# APU.net
KiCad netlist of a schematic drawn in EAGLE
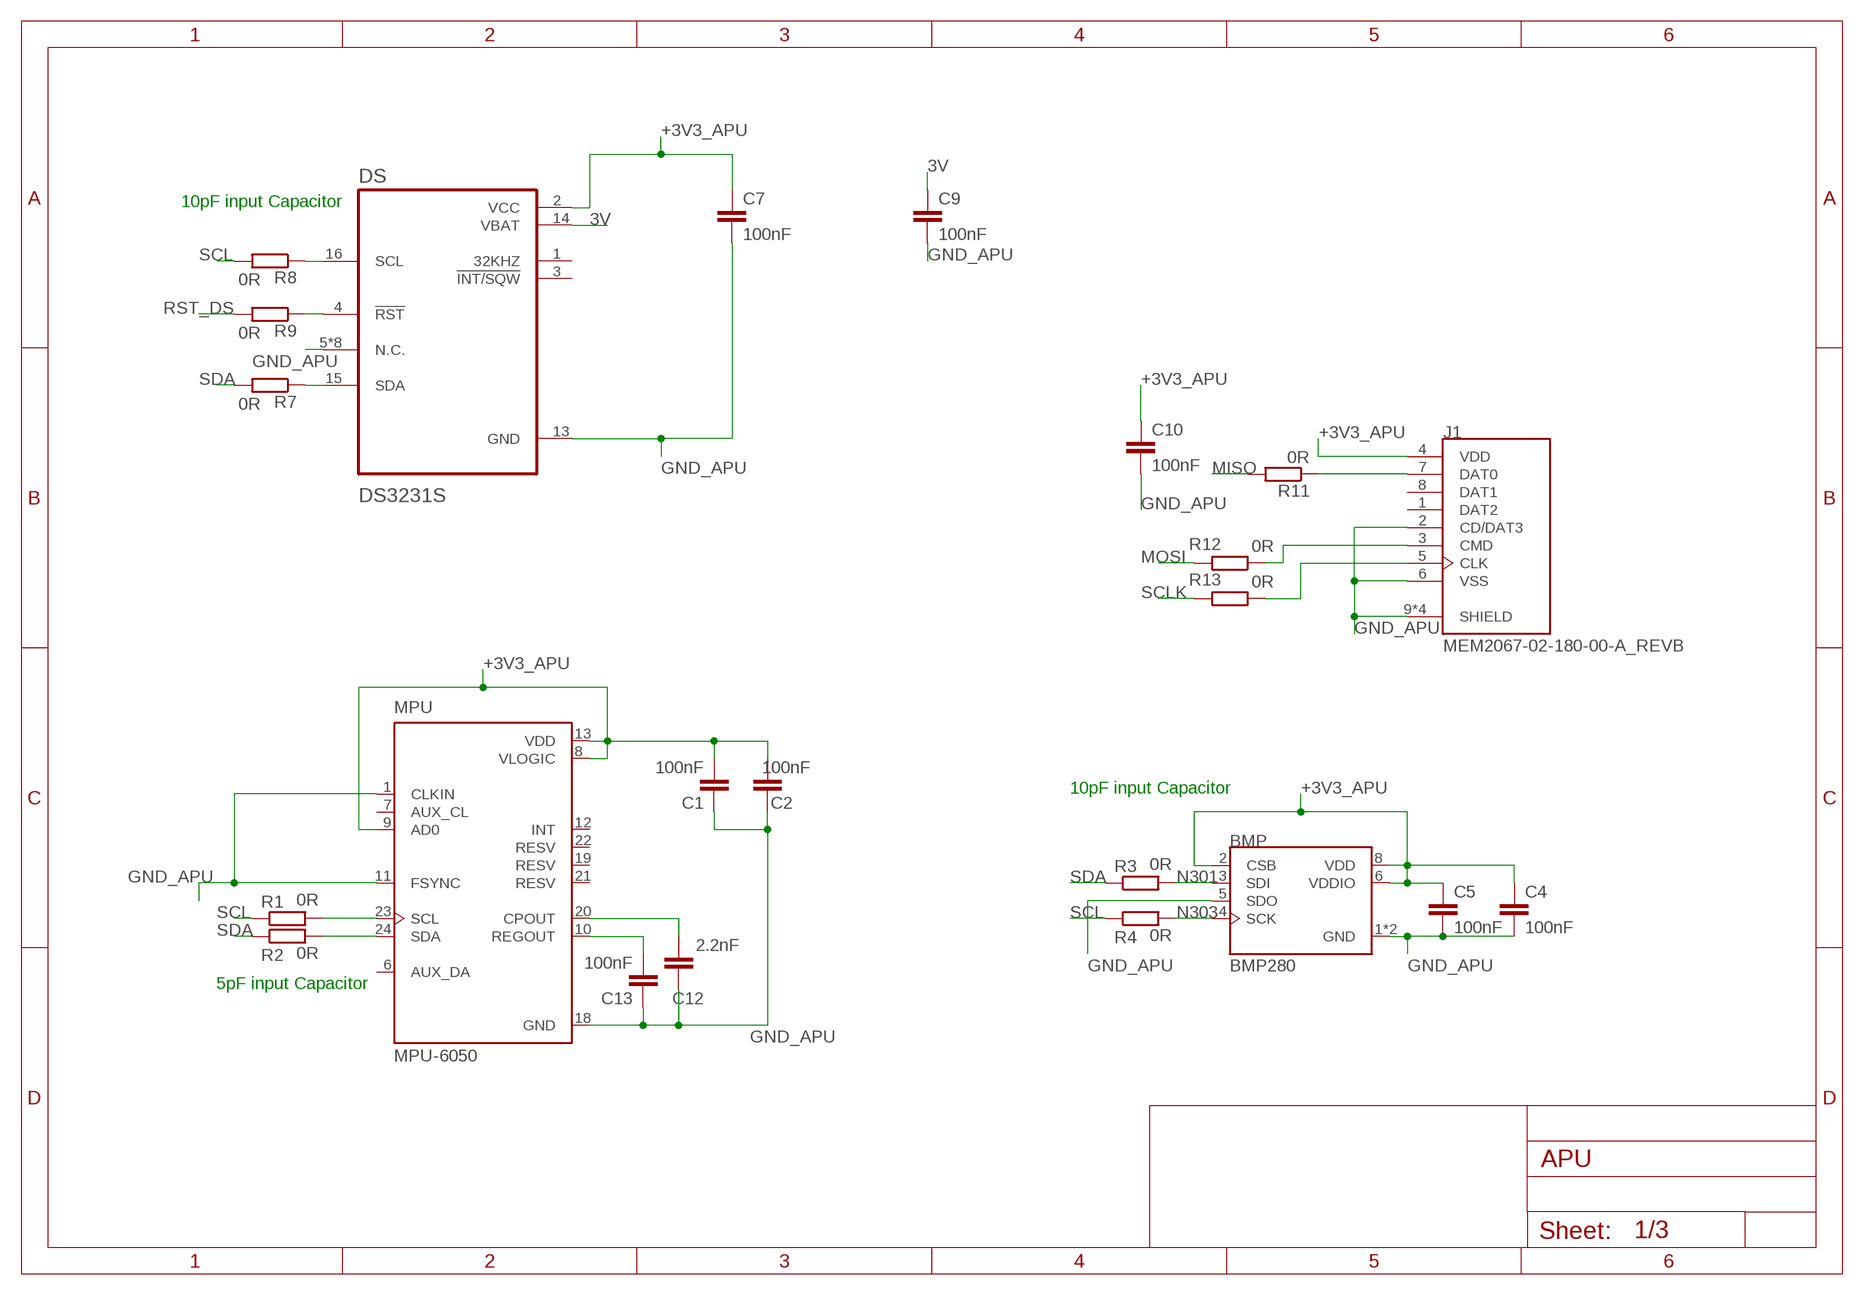
[diagram p0: schematic, sheet 1]
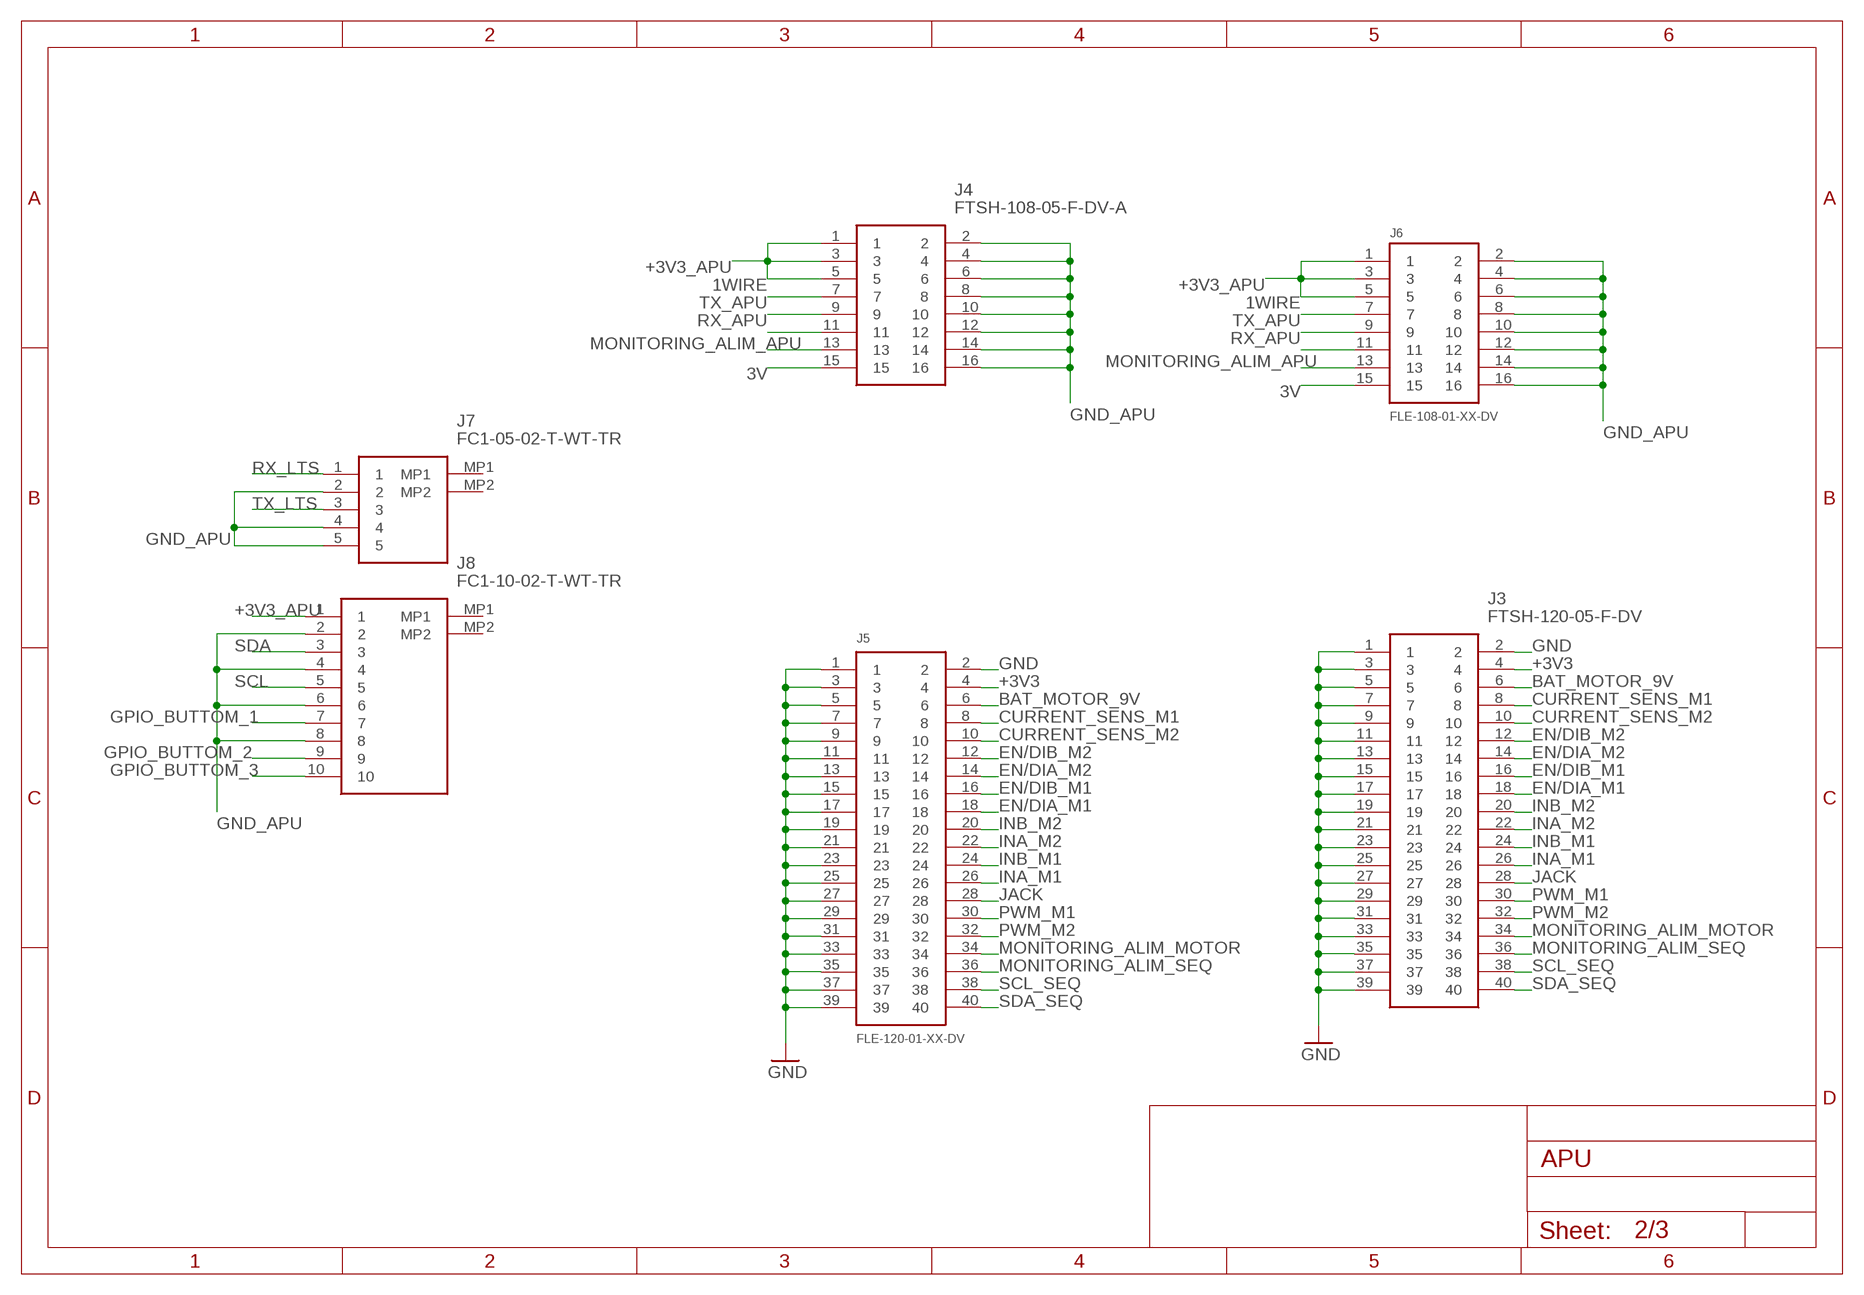
[diagram p1: schematic, sheet 2]
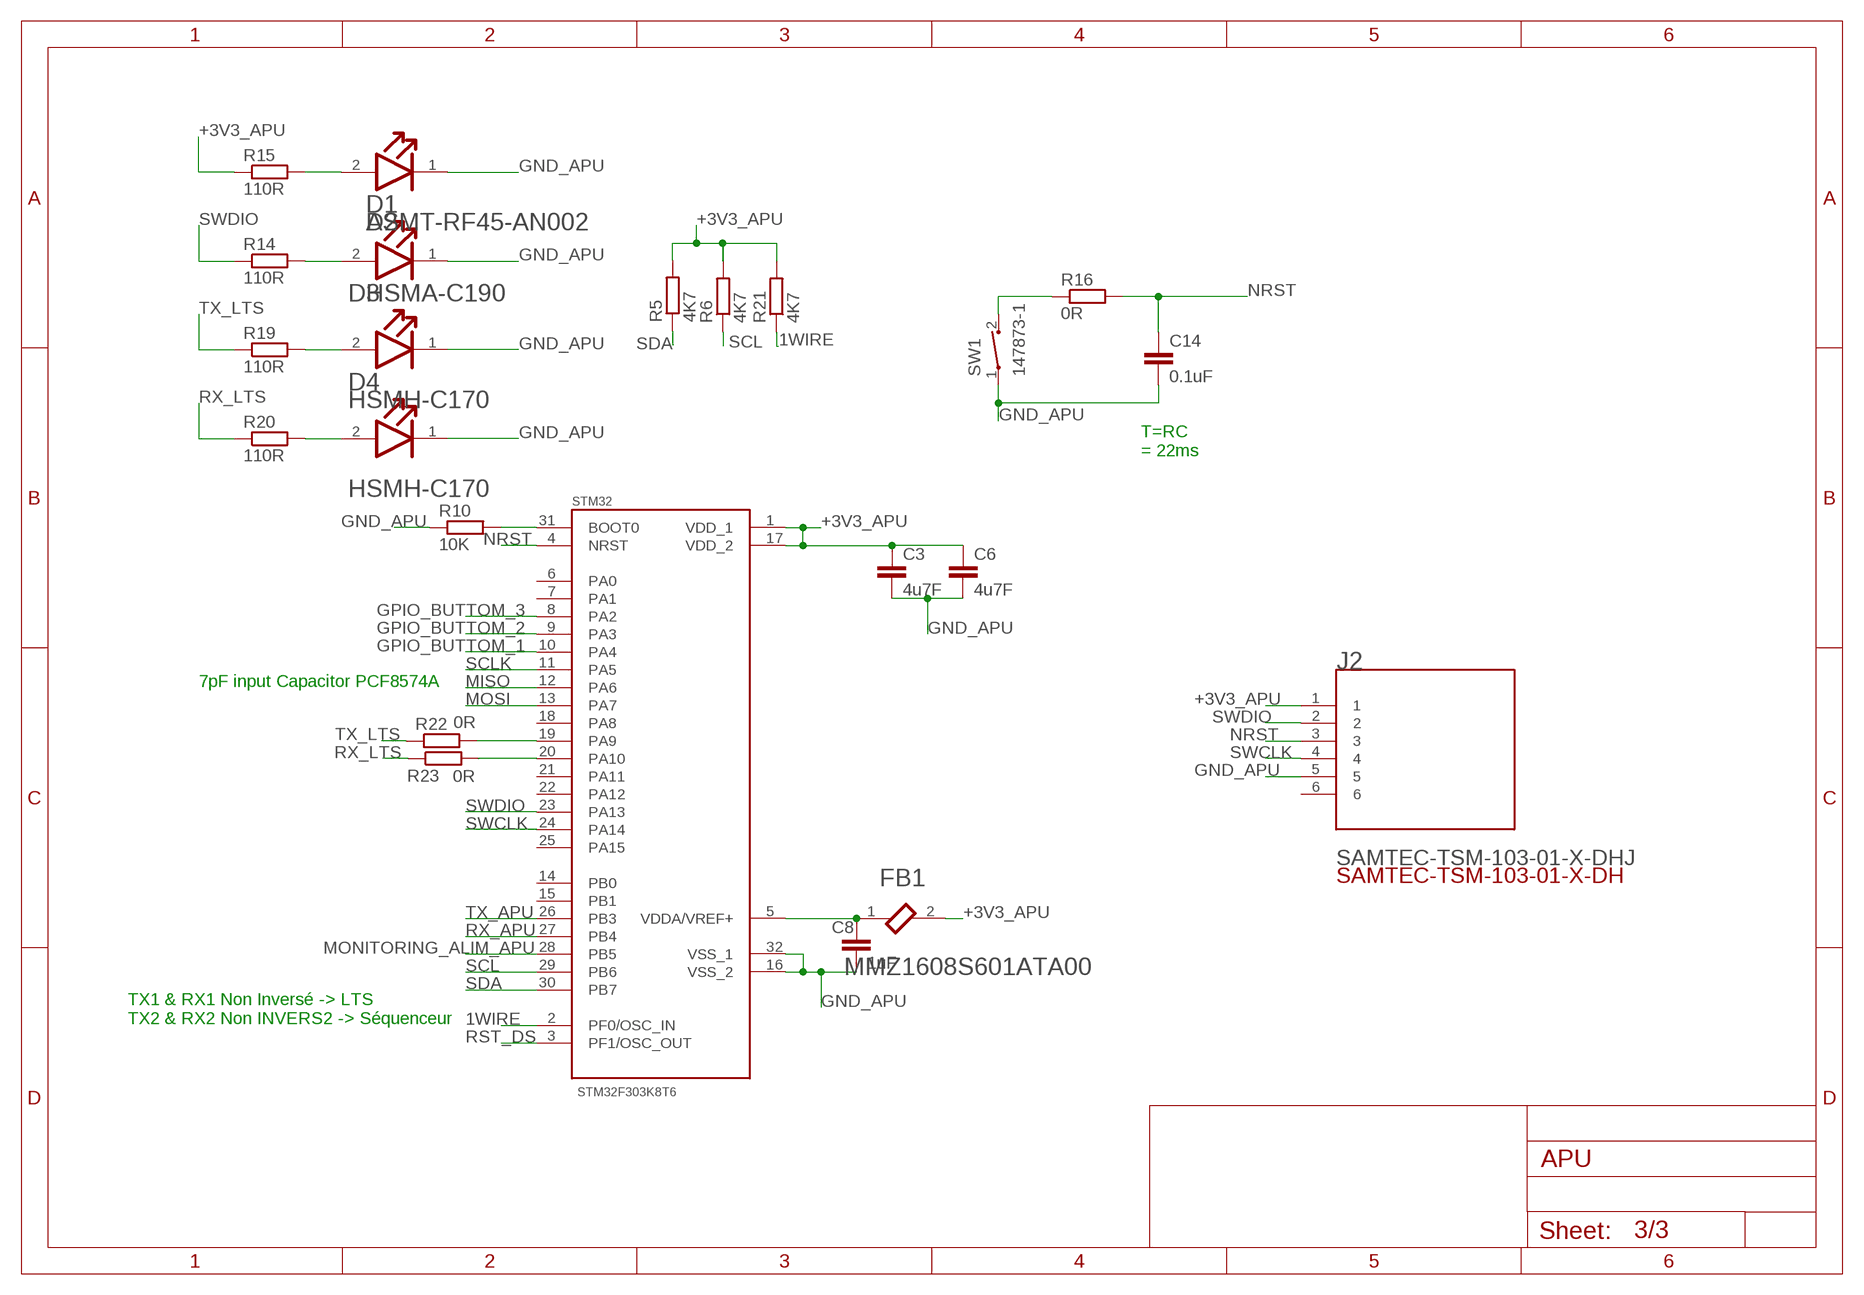
[diagram p2: schematic, sheet 3]

(export (version "E")
  (design (tool "Eeschema 10.0.6"))
  (components
    (comp (ref "BMP")
      (value "BMP280")
      (footprint "eagle-import:XDCR_BMP280")
      (fields (field (name "MF") "Bosch"))
      (libsource (lib "eagle-import") (part "BMP280"))
    )
    (comp (ref "C1")
      (value "100nF")
      (footprint "eagle-import:C0805")
      (libsource (lib "eagle-import") (part "C-EUC0805"))
    )
    (comp (ref "C2")
      (value "100nF")
      (footprint "eagle-import:C0805")
      (libsource (lib "eagle-import") (part "C-EUC0805"))
    )
    (comp (ref "C4")
      (value "100nF")
      (footprint "eagle-import:C0805")
      (libsource (lib "eagle-import") (part "C-EUC0805"))
    )
    (comp (ref "C5")
      (value "100nF")
      (footprint "eagle-import:C0805")
      (libsource (lib "eagle-import") (part "C-EUC0805"))
    )
    (comp (ref "C7")
      (value "100nF")
      (footprint "eagle-import:C0805")
      (libsource (lib "eagle-import") (part "C-EUC0805"))
    )
    (comp (ref "C9")
      (value "100nF")
      (footprint "eagle-import:C0805")
      (libsource (lib "eagle-import") (part "C-EUC0805"))
    )
    (comp (ref "C10")
      (value "100nF")
      (footprint "eagle-import:C0805")
      (libsource (lib "eagle-import") (part "C-EUC0805"))
    )
    (comp (ref "C12")
      (value "2.2nF")
      (footprint "eagle-import:C0805")
      (libsource (lib "eagle-import") (part "C-EUC0805"))
    )
    (comp (ref "C13")
      (value "100nF")
      (footprint "eagle-import:C0805")
      (libsource (lib "eagle-import") (part "C-EUC0805"))
    )
    (comp (ref "DS")
      (value "DS3231S")
      (footprint "eagle-import:SOIC127P1032X265-16N")
      (fields (field (name "MF") "Maxim Integrated"))
      (libsource (lib "eagle-import") (part "DS3231S"))
    )
    (comp (ref "J1")
      (value "MEM2067-02-180-00-A_REVB")
      (footprint "eagle-import:GCT_MEM2067-02-180-00-A_REVB")
      (fields (field (name "MF") "Global Connector Technology") (field (name "MP") "MEM2067-02-180-00-A"))
      (libsource (lib "eagle-import") (part "MEM2067-02-180-00-A_REVB"))
    )
    (comp (ref "MPU")
      (value "MPU-6050")
      (footprint "eagle-import:QFN50P400X400X95-24N")
      (fields (field (name "MF") "TDK InvenSense"))
      (libsource (lib "eagle-import") (part "MPU-6050"))
    )
    (comp (ref "R1")
      (value "0R")
      (footprint "eagle-import:R0603")
      (libsource (lib "eagle-import") (part "R-EU_R0603"))
    )
    (comp (ref "R2")
      (value "0R")
      (footprint "eagle-import:R0603")
      (libsource (lib "eagle-import") (part "R-EU_R0603"))
    )
    (comp (ref "R3")
      (value "0R")
      (footprint "eagle-import:R0603")
      (libsource (lib "eagle-import") (part "R-EU_R0603"))
    )
    (comp (ref "R4")
      (value "0R")
      (footprint "eagle-import:R0603")
      (libsource (lib "eagle-import") (part "R-EU_R0603"))
    )
    (comp (ref "R7")
      (value "0R")
      (footprint "eagle-import:R0603")
      (libsource (lib "eagle-import") (part "R-EU_R0603"))
    )
    (comp (ref "R8")
      (value "0R")
      (footprint "eagle-import:R0603")
      (libsource (lib "eagle-import") (part "R-EU_R0603"))
    )
    (comp (ref "R9")
      (value "0R")
      (footprint "eagle-import:R0603")
      (libsource (lib "eagle-import") (part "R-EU_R0603"))
    )
    (comp (ref "R11")
      (value "0R")
      (footprint "eagle-import:R0603")
      (libsource (lib "eagle-import") (part "R-EU_R0603"))
    )
    (comp (ref "R12")
      (value "0R")
      (footprint "eagle-import:R0603")
      (libsource (lib "eagle-import") (part "R-EU_R0603"))
    )
    (comp (ref "R13")
      (value "0R")
      (footprint "eagle-import:R0603")
      (libsource (lib "eagle-import") (part "R-EU_R0603"))
    )
    (comp (ref "C3")
      (value "4u7F")
      (footprint "eagle-import:C0805K")
      (libsource (lib "eagle-import") (part "C-EUC0805K"))
    )
    (comp (ref "C6")
      (value "4u7F")
      (footprint "eagle-import:C0805K")
      (libsource (lib "eagle-import") (part "C-EUC0805K"))
    )
    (comp (ref "C8")
      (value "1uF")
      (footprint "eagle-import:C0805K")
      (libsource (lib "eagle-import") (part "C-EUC0805K"))
    )
    (comp (ref "C14")
      (value "0.1uF")
      (footprint "eagle-import:C0805K")
      (libsource (lib "eagle-import") (part "C-EUC0805K"))
    )
    (comp (ref "D1")
      (value "BROADCOM_ASMT-RF45-AN002BROADCOM_ASMT-RF45-AN002_0_0")
      (footprint "eagle-import:BROADCOM_ASMT-RF45-AN002_0")
      (fields
        (field (name "DIGIKEY_PART_NUMBER") "516-2522-1-ND")
        (field (name "MF") "Broadcom")
        (field (name "MOUSER_PART_NUMBER") "630-ASMT-RF45-AN002")
      )
      (libsource (lib "eagle-import") (part "BROADCOM_ASMT-RF45-AN002BROADCOM_ASMT-RF45-AN002_0_0"))
    )
    (comp (ref "D2")
      (value "BROADCOM_HSMA-C190BROADCOM_HSMA-C190_0_0")
      (footprint "eagle-import:BROADCOM_HSMA-C190_0")
      (fields
        (field (name "DIGIKEY_PART_NUMBER") "516-1423-1-ND")
        (field (name "MF") "Broadcom")
        (field (name "MOUSER_PART_NUMBER") "630-HSMA-C190")
      )
      (libsource (lib "eagle-import") (part "BROADCOM_HSMA-C190BROADCOM_HSMA-C190_0_0"))
    )
    (comp (ref "D3")
      (value "BROADCOM_HSMH-C170BROADCOM_HSMH-C170_0_0")
      (footprint "eagle-import:BROADCOM_HSMH-C170_0")
      (fields
        (field (name "DIGIKEY_PART_NUMBER") "516-1427-1-ND")
        (field (name "MF") "Broadcom")
        (field (name "MOUSER_PART_NUMBER") "630-HSMH-C170")
      )
      (libsource (lib "eagle-import") (part "BROADCOM_HSMH-C170BROADCOM_HSMH-C170_0_0"))
    )
    (comp (ref "D4")
      (value "BROADCOM_HSMH-C170BROADCOM_HSMH-C170_0_0")
      (footprint "eagle-import:BROADCOM_HSMH-C170_0")
      (fields
        (field (name "DIGIKEY_PART_NUMBER") "516-1427-1-ND")
        (field (name "MF") "Broadcom")
        (field (name "MOUSER_PART_NUMBER") "630-HSMH-C170")
      )
      (libsource (lib "eagle-import") (part "BROADCOM_HSMH-C170BROADCOM_HSMH-C170_0_0"))
    )
    (comp (ref "FB1")
      (value "TDK_MMZ1608S601ATA00TDK_MMZ1608S601ATA00_0_0")
      (footprint "eagle-import:TDK_MMZ1608S601ATA00_0")
      (fields
        (field (name "MF") "TDK")
        (field (name "MPN") "MMZ1608S601ATA00")
        (field (name "TOLERANCE") "25%")
      )
      (libsource (lib "eagle-import") (part "TDK_MMZ1608S601ATA00TDK_MMZ1608S601ATA00_0_0"))
    )
    (comp (ref "J2")
      (value "SAMTEC-TSM-103-01-X-DHJ")
      (footprint "eagle-import:SAMTEC-TSM-103-01-X-DH")
      (fields (field (name "MF") "Samtec Inc.") (field (name "MP") "TSM-103-01-F-DH"))
      (libsource (lib "eagle-import") (part "SAMTEC-TSM-103-01-X-DHJ"))
    )
    (comp (ref "R5")
      (value "4K7")
      (footprint "eagle-import:R0603")
      (libsource (lib "eagle-import") (part "R-EU_R0603"))
    )
    (comp (ref "R6")
      (value "4K7")
      (footprint "eagle-import:R0603")
      (libsource (lib "eagle-import") (part "R-EU_R0603"))
    )
    (comp (ref "R10")
      (value "10K")
      (footprint "eagle-import:R0603")
      (libsource (lib "eagle-import") (part "R-EU_R0603"))
    )
    (comp (ref "R14")
      (value "110R")
      (footprint "eagle-import:R0603")
      (libsource (lib "eagle-import") (part "R-EU_R0603"))
    )
    (comp (ref "R15")
      (value "110R")
      (footprint "eagle-import:R0603")
      (libsource (lib "eagle-import") (part "R-EU_R0603"))
    )
    (comp (ref "R16")
      (value "0R")
      (footprint "eagle-import:R0603")
      (libsource (lib "eagle-import") (part "R-EU_R0603"))
    )
    (comp (ref "R19")
      (value "110R")
      (footprint "eagle-import:R0603")
      (libsource (lib "eagle-import") (part "R-EU_R0603"))
    )
    (comp (ref "R20")
      (value "110R")
      (footprint "eagle-import:R0603")
      (libsource (lib "eagle-import") (part "R-EU_R0603"))
    )
    (comp (ref "R21")
      (value "4K7")
      (footprint "eagle-import:R0603")
      (libsource (lib "eagle-import") (part "R-EU_R0603"))
    )
    (comp (ref "R22")
      (value "0R")
      (footprint "eagle-import:R0603")
      (libsource (lib "eagle-import") (part "R-EU_R0603"))
    )
    (comp (ref "R23")
      (value "0R")
      (footprint "eagle-import:R0603")
      (libsource (lib "eagle-import") (part "R-EU_R0603"))
    )
    (comp (ref "STM32")
      (value "STM32F303K8T6")
      (footprint "eagle-import:QFP80P900X900X160-32N")
      (fields (field (name "MANUFACTURER") "ST microelectronics"))
      (libsource (lib "eagle-import") (part "STM32F303K8T6"))
    )
    (comp (ref "SW1")
      (value "147873-1")
      (footprint "eagle-import:SW_147873-1")
      (fields (field (name "MF") "TE Connectivity"))
      (libsource (lib "eagle-import") (part "147873-1"))
    )
    (comp (ref "J3")
      (value "FTSH-120-05-F-DV")
      (footprint "eagle-import:FTSH-120-XX-YYY-DV")
      (libsource (lib "eagle-import") (part "FTSH-120-05-F-DV"))
    )
    (comp (ref "J4")
      (value "FTSH-108-05-F-DV-A")
      (footprint "eagle-import:FTSH-108-XX-YYY-DV-A")
      (fields (field (name "MOUSER_PART_NUMBER") "200-FTSH10805FDVA"))
      (libsource (lib "eagle-import") (part "FTSH-108-05-F-DV-A"))
    )
    (comp (ref "J5")
      (value "FLE-120-01-XX-DV")
      (footprint "eagle-import:FLE-120-01-XX-DV")
      (fields (field (name "MF") "Samtec") (field (name "MP") "FLE-120-01-G-DV"))
      (libsource (lib "eagle-import") (part "FLE-120-01-XX-DV"))
    )
    (comp (ref "J6")
      (value "FLE-108-01-XX-DV")
      (footprint "eagle-import:FLE-108-01-XX-DV")
      (fields (field (name "MF") "Samtec") (field (name "MP") "FLE-108-01-G-DV"))
      (libsource (lib "eagle-import") (part "FLE-108-01-XX-DV"))
    )
    (comp (ref "J7")
      (value "FC1-05-02-T-WT-TR")
      (footprint "eagle-import:FC10502TWTTR")
      (fields (field (name "MOUSER_PART_NUMBER") "200-FC10502TWTTR"))
      (libsource (lib "eagle-import") (part "FC1-05-02-T-WT-TR"))
    )
    (comp (ref "J8")
      (value "FC1-10-02-T-WT-TR")
      (footprint "eagle-import:FC11002TWTTR")
      (fields (field (name "MOUSER_PART_NUMBER") "200-FC11002TWTTR"))
      (libsource (lib "eagle-import") (part "FC1-10-02-T-WT-TR"))
    )
  )
  (nets
    (net (code "1") (name "+3V3") (class "Default")
      (node (ref "J3") (pin "4") (pinfunction "4_4") (pintype "bidirectional"))
      (node (ref "J5") (pin "4") (pinfunction "4_4") (pintype "bidirectional"))
    )
    (net (code "2") (name "+3V3_APU") (class "Default")
      (node (ref "BMP") (pin "2") (pinfunction "CSB_2") (pintype "input"))
      (node (ref "BMP") (pin "6") (pinfunction "VDDIO_6") (pintype "power_in"))
      (node (ref "BMP") (pin "8") (pinfunction "VDD_8") (pintype "power_in"))
      (node (ref "C1") (pin "2") (pinfunction "2_2") (pintype "passive"))
      (node (ref "C10") (pin "1") (pinfunction "1_1") (pintype "passive"))
      (node (ref "C2") (pin "2") (pinfunction "2_2") (pintype "passive"))
      (node (ref "C3") (pin "1") (pinfunction "1_1") (pintype "passive"))
      (node (ref "C4") (pin "1") (pinfunction "1_1") (pintype "passive"))
      (node (ref "C5") (pin "1") (pinfunction "1_1") (pintype "passive"))
      (node (ref "C6") (pin "1") (pinfunction "1_1") (pintype "passive"))
      (node (ref "C7") (pin "1") (pinfunction "1_1") (pintype "passive"))
      (node (ref "DS") (pin "2") (pinfunction "VCC_2") (pintype "power_in"))
      (node (ref "FB1") (pin "2") (pinfunction "2_2") (pintype "passive"))
      (node (ref "J1") (pin "4") (pinfunction "VDD_4") (pintype "power_in"))
      (node (ref "J2") (pin "1") (pinfunction "1_1") (pintype "bidirectional"))
      (node (ref "J4") (pin "1") (pinfunction "1_1") (pintype "bidirectional"))
      (node (ref "J4") (pin "3") (pinfunction "3_3") (pintype "bidirectional"))
      (node (ref "J4") (pin "5") (pinfunction "5_5") (pintype "bidirectional"))
      (node (ref "J6") (pin "1") (pinfunction "1_1") (pintype "bidirectional"))
      (node (ref "J6") (pin "3") (pinfunction "3_3") (pintype "bidirectional"))
      (node (ref "J6") (pin "5") (pinfunction "5_5") (pintype "bidirectional"))
      (node (ref "J8") (pin "1") (pinfunction "1_1") (pintype "bidirectional"))
      (node (ref "MPU") (pin "13") (pinfunction "VDD_13") (pintype "power_in"))
      (node (ref "MPU") (pin "8") (pinfunction "VLOGIC_8") (pintype "power_in"))
      (node (ref "MPU") (pin "9") (pinfunction "AD0_9") (pintype "input"))
      (node (ref "R15") (pin "1") (pinfunction "1_1") (pintype "passive"))
      (node (ref "R21") (pin "2") (pinfunction "2_2") (pintype "passive"))
      (node (ref "R5") (pin "2") (pinfunction "2_2") (pintype "passive"))
      (node (ref "R6") (pin "2") (pinfunction "2_2") (pintype "passive"))
      (node (ref "STM32") (pin "1") (pinfunction "VDD_1_1") (pintype "power_in"))
      (node (ref "STM32") (pin "17") (pinfunction "VDD_2_17") (pintype "power_in"))
    )
    (net (code "3") (name "1WIRE") (class "Default")
      (node (ref "J4") (pin "7") (pinfunction "7_7") (pintype "bidirectional"))
      (node (ref "J6") (pin "7") (pinfunction "7_7") (pintype "bidirectional"))
      (node (ref "R21") (pin "1") (pinfunction "1_1") (pintype "passive"))
      (node (ref "STM32") (pin "2") (pinfunction "PF0/OSC_IN_2") (pintype "bidirectional"))
    )
    (net (code "4") (name "3V") (class "Default")
      (node (ref "C9") (pin "1") (pinfunction "1_1") (pintype "passive"))
      (node (ref "DS") (pin "14") (pinfunction "VBAT_14") (pintype "power_in"))
      (node (ref "J4") (pin "15") (pinfunction "15_15") (pintype "bidirectional"))
      (node (ref "J6") (pin "15") (pinfunction "15_15") (pintype "bidirectional"))
    )
    (net (code "5") (name "BAT_MOTOR_9V") (class "Default")
      (node (ref "J3") (pin "6") (pinfunction "6_6") (pintype "bidirectional"))
      (node (ref "J5") (pin "6") (pinfunction "6_6") (pintype "bidirectional"))
    )
    (net (code "6") (name "CURRENT_SENS_M1") (class "Default")
      (node (ref "J3") (pin "8") (pinfunction "8_8") (pintype "bidirectional"))
      (node (ref "J5") (pin "8") (pinfunction "8_8") (pintype "bidirectional"))
    )
    (net (code "7") (name "CURRENT_SENS_M2") (class "Default")
      (node (ref "J3") (pin "10") (pinfunction "10_10") (pintype "bidirectional"))
      (node (ref "J5") (pin "10") (pinfunction "10_10") (pintype "bidirectional"))
    )
    (net (code "8") (name "EN{slash}DIA_M1") (class "Default")
      (node (ref "J3") (pin "18") (pinfunction "18_18") (pintype "bidirectional"))
      (node (ref "J5") (pin "18") (pinfunction "18_18") (pintype "bidirectional"))
    )
    (net (code "9") (name "EN{slash}DIA_M2") (class "Default")
      (node (ref "J3") (pin "14") (pinfunction "14_14") (pintype "bidirectional"))
      (node (ref "J5") (pin "14") (pinfunction "14_14") (pintype "bidirectional"))
    )
    (net (code "10") (name "EN{slash}DIB_M1") (class "Default")
      (node (ref "J3") (pin "16") (pinfunction "16_16") (pintype "bidirectional"))
      (node (ref "J5") (pin "16") (pinfunction "16_16") (pintype "bidirectional"))
    )
    (net (code "11") (name "EN{slash}DIB_M2") (class "Default")
      (node (ref "J3") (pin "12") (pinfunction "12_12") (pintype "bidirectional"))
      (node (ref "J5") (pin "12") (pinfunction "12_12") (pintype "bidirectional"))
    )
    (net (code "12") (name "GND") (class "Default")
      (node (ref "J3") (pin "1") (pinfunction "1_1") (pintype "bidirectional"))
      (node (ref "J3") (pin "11") (pinfunction "11_11") (pintype "bidirectional"))
      (node (ref "J3") (pin "13") (pinfunction "13_13") (pintype "bidirectional"))
      (node (ref "J3") (pin "15") (pinfunction "15_15") (pintype "bidirectional"))
      (node (ref "J3") (pin "17") (pinfunction "17_17") (pintype "bidirectional"))
      (node (ref "J3") (pin "19") (pinfunction "19_19") (pintype "bidirectional"))
      (node (ref "J3") (pin "2") (pinfunction "2_2") (pintype "bidirectional"))
      (node (ref "J3") (pin "21") (pinfunction "21_21") (pintype "bidirectional"))
      (node (ref "J3") (pin "23") (pinfunction "23_23") (pintype "bidirectional"))
      (node (ref "J3") (pin "25") (pinfunction "25_25") (pintype "bidirectional"))
      (node (ref "J3") (pin "27") (pinfunction "27_27") (pintype "bidirectional"))
      (node (ref "J3") (pin "29") (pinfunction "29_29") (pintype "bidirectional"))
      (node (ref "J3") (pin "3") (pinfunction "3_3") (pintype "bidirectional"))
      (node (ref "J3") (pin "31") (pinfunction "31_31") (pintype "bidirectional"))
      (node (ref "J3") (pin "33") (pinfunction "33_33") (pintype "bidirectional"))
      (node (ref "J3") (pin "35") (pinfunction "35_35") (pintype "bidirectional"))
      (node (ref "J3") (pin "37") (pinfunction "37_37") (pintype "bidirectional"))
      (node (ref "J3") (pin "39") (pinfunction "39_39") (pintype "bidirectional"))
      (node (ref "J3") (pin "5") (pinfunction "5_5") (pintype "bidirectional"))
      (node (ref "J3") (pin "7") (pinfunction "7_7") (pintype "bidirectional"))
      (node (ref "J3") (pin "9") (pinfunction "9_9") (pintype "bidirectional"))
      (node (ref "J5") (pin "1") (pinfunction "1_1") (pintype "bidirectional"))
      (node (ref "J5") (pin "11") (pinfunction "11_11") (pintype "bidirectional"))
      (node (ref "J5") (pin "13") (pinfunction "13_13") (pintype "bidirectional"))
      (node (ref "J5") (pin "15") (pinfunction "15_15") (pintype "bidirectional"))
      (node (ref "J5") (pin "17") (pinfunction "17_17") (pintype "bidirectional"))
      (node (ref "J5") (pin "19") (pinfunction "19_19") (pintype "bidirectional"))
      (node (ref "J5") (pin "2") (pinfunction "2_2") (pintype "bidirectional"))
      (node (ref "J5") (pin "21") (pinfunction "21_21") (pintype "bidirectional"))
      (node (ref "J5") (pin "23") (pinfunction "23_23") (pintype "bidirectional"))
      (node (ref "J5") (pin "25") (pinfunction "25_25") (pintype "bidirectional"))
      (node (ref "J5") (pin "27") (pinfunction "27_27") (pintype "bidirectional"))
      (node (ref "J5") (pin "29") (pinfunction "29_29") (pintype "bidirectional"))
      (node (ref "J5") (pin "3") (pinfunction "3_3") (pintype "bidirectional"))
      (node (ref "J5") (pin "31") (pinfunction "31_31") (pintype "bidirectional"))
      (node (ref "J5") (pin "33") (pinfunction "33_33") (pintype "bidirectional"))
      (node (ref "J5") (pin "35") (pinfunction "35_35") (pintype "bidirectional"))
      (node (ref "J5") (pin "37") (pinfunction "37_37") (pintype "bidirectional"))
      (node (ref "J5") (pin "39") (pinfunction "39_39") (pintype "bidirectional"))
      (node (ref "J5") (pin "5") (pinfunction "5_5") (pintype "bidirectional"))
      (node (ref "J5") (pin "7") (pinfunction "7_7") (pintype "bidirectional"))
      (node (ref "J5") (pin "9") (pinfunction "9_9") (pintype "bidirectional"))
    )
    (net (code "13") (name "GND_APU") (class "Default")
      (node (ref "BMP") (pin "1") (pinfunction "GND_1") (pintype "power_in"))
      (node (ref "BMP") (pin "5") (pinfunction "SDO_5") (pintype "bidirectional"))
      (node (ref "BMP") (pin "7") (pinfunction "GND_7") (pintype "power_in"))
      (node (ref "C1") (pin "1") (pinfunction "1_1") (pintype "passive"))
      (node (ref "C10") (pin "2") (pinfunction "2_2") (pintype "passive"))
      (node (ref "C12") (pin "1") (pinfunction "1_1") (pintype "passive"))
      (node (ref "C13") (pin "1") (pinfunction "1_1") (pintype "passive"))
      (node (ref "C14") (pin "2") (pinfunction "2_2") (pintype "passive"))
      (node (ref "C2") (pin "1") (pinfunction "1_1") (pintype "passive"))
      (node (ref "C3") (pin "2") (pinfunction "2_2") (pintype "passive"))
      (node (ref "C4") (pin "2") (pinfunction "2_2") (pintype "passive"))
      (node (ref "C5") (pin "2") (pinfunction "2_2") (pintype "passive"))
      (node (ref "C6") (pin "2") (pinfunction "2_2") (pintype "passive"))
      (node (ref "C7") (pin "2") (pinfunction "2_2") (pintype "passive"))
      (node (ref "C8") (pin "2") (pinfunction "2_2") (pintype "passive"))
      (node (ref "C9") (pin "2") (pinfunction "2_2") (pintype "passive"))
      (node (ref "D1") (pin "1") (pinfunction "CATHODE_1") (pintype "passive"))
      (node (ref "D2") (pin "1") (pinfunction "CATHODE_1") (pintype "passive"))
      (node (ref "D3") (pin "1") (pinfunction "CATHODE_1") (pintype "passive"))
      (node (ref "D4") (pin "1") (pinfunction "CATHODE_1") (pintype "passive"))
      (node (ref "DS") (pin "10") (pinfunction "N.C._10") (pintype "bidirectional"))
      (node (ref "DS") (pin "11") (pinfunction "N.C._11") (pintype "bidirectional"))
      (node (ref "DS") (pin "12") (pinfunction "N.C._12") (pintype "bidirectional"))
      (node (ref "DS") (pin "13") (pinfunction "GND_13") (pintype "power_in"))
      (node (ref "DS") (pin "5") (pinfunction "N.C._5") (pintype "bidirectional"))
      (node (ref "DS") (pin "6") (pinfunction "N.C._6") (pintype "bidirectional"))
      (node (ref "DS") (pin "7") (pinfunction "N.C._7") (pintype "bidirectional"))
      (node (ref "DS") (pin "8") (pinfunction "N.C._8") (pintype "bidirectional"))
      (node (ref "DS") (pin "9") (pinfunction "N.C._9") (pintype "bidirectional"))
      (node (ref "J1") (pin "10") (pinfunction "SHIELD_10") (pintype "passive"))
      (node (ref "J1") (pin "11") (pinfunction "SHIELD_11") (pintype "passive"))
      (node (ref "J1") (pin "12") (pinfunction "SHIELD_12") (pintype "passive"))
      (node (ref "J1") (pin "2") (pinfunction "CD/DAT3_2") (pintype "bidirectional"))
      (node (ref "J1") (pin "6") (pinfunction "VSS_6") (pintype "power_in"))
      (node (ref "J1") (pin "9") (pinfunction "SHIELD_9") (pintype "passive"))
      (node (ref "J2") (pin "5") (pinfunction "5_5") (pintype "bidirectional"))
      (node (ref "J4") (pin "10") (pinfunction "10_10") (pintype "bidirectional"))
      (node (ref "J4") (pin "12") (pinfunction "12_12") (pintype "bidirectional"))
      (node (ref "J4") (pin "14") (pinfunction "14_14") (pintype "bidirectional"))
      (node (ref "J4") (pin "16") (pinfunction "16_16") (pintype "bidirectional"))
      (node (ref "J4") (pin "2") (pinfunction "2_2") (pintype "bidirectional"))
      (node (ref "J4") (pin "4") (pinfunction "4_4") (pintype "bidirectional"))
      (node (ref "J4") (pin "6") (pinfunction "6_6") (pintype "bidirectional"))
      (node (ref "J4") (pin "8") (pinfunction "8_8") (pintype "bidirectional"))
      (node (ref "J6") (pin "10") (pinfunction "10_10") (pintype "bidirectional"))
      (node (ref "J6") (pin "12") (pinfunction "12_12") (pintype "bidirectional"))
      (node (ref "J6") (pin "14") (pinfunction "14_14") (pintype "bidirectional"))
      (node (ref "J6") (pin "16") (pinfunction "16_16") (pintype "bidirectional"))
      (node (ref "J6") (pin "2") (pinfunction "2_2") (pintype "bidirectional"))
      (node (ref "J6") (pin "4") (pinfunction "4_4") (pintype "bidirectional"))
      (node (ref "J6") (pin "6") (pinfunction "6_6") (pintype "bidirectional"))
      (node (ref "J6") (pin "8") (pinfunction "8_8") (pintype "bidirectional"))
      (node (ref "J7") (pin "2") (pinfunction "2_2") (pintype "bidirectional"))
      (node (ref "J7") (pin "4") (pinfunction "4_4") (pintype "bidirectional"))
      (node (ref "J7") (pin "5") (pinfunction "5_5") (pintype "bidirectional"))
      (node (ref "J8") (pin "2") (pinfunction "2_2") (pintype "bidirectional"))
      (node (ref "J8") (pin "4") (pinfunction "4_4") (pintype "bidirectional"))
      (node (ref "J8") (pin "6") (pinfunction "6_6") (pintype "bidirectional"))
      (node (ref "J8") (pin "8") (pinfunction "8_8") (pintype "bidirectional"))
      (node (ref "MPU") (pin "1") (pinfunction "CLKIN_1") (pintype "input"))
      (node (ref "MPU") (pin "11") (pinfunction "FSYNC_11") (pintype "input"))
      (node (ref "MPU") (pin "18") (pinfunction "GND_18") (pintype "power_in"))
      (node (ref "R10") (pin "1") (pinfunction "1_1") (pintype "passive"))
      (node (ref "STM32") (pin "16") (pinfunction "VSS_2_16") (pintype "power_in"))
      (node (ref "STM32") (pin "32") (pinfunction "VSS_1_32") (pintype "power_in"))
      (node (ref "SW1") (pin "1") (pinfunction "1_1") (pintype "passive"))
    )
    (net (code "14") (name "GPIO_BUTTOM_1") (class "Default")
      (node (ref "J8") (pin "7") (pinfunction "7_7") (pintype "bidirectional"))
      (node (ref "STM32") (pin "10") (pinfunction "PA4_10") (pintype "bidirectional"))
    )
    (net (code "15") (name "GPIO_BUTTOM_2") (class "Default")
      (node (ref "J8") (pin "9") (pinfunction "9_9") (pintype "bidirectional"))
      (node (ref "STM32") (pin "9") (pinfunction "PA3_9") (pintype "bidirectional"))
    )
    (net (code "16") (name "GPIO_BUTTOM_3") (class "Default")
      (node (ref "J8") (pin "10") (pinfunction "10_10") (pintype "bidirectional"))
      (node (ref "STM32") (pin "8") (pinfunction "PA2_8") (pintype "bidirectional"))
    )
    (net (code "17") (name "INA_M1") (class "Default")
      (node (ref "J3") (pin "26") (pinfunction "26_26") (pintype "bidirectional"))
      (node (ref "J5") (pin "26") (pinfunction "26_26") (pintype "bidirectional"))
    )
    (net (code "18") (name "INA_M2") (class "Default")
      (node (ref "J3") (pin "22") (pinfunction "22_22") (pintype "bidirectional"))
      (node (ref "J5") (pin "22") (pinfunction "22_22") (pintype "bidirectional"))
    )
    (net (code "19") (name "INB_M1") (class "Default")
      (node (ref "J3") (pin "24") (pinfunction "24_24") (pintype "bidirectional"))
      (node (ref "J5") (pin "24") (pinfunction "24_24") (pintype "bidirectional"))
    )
    (net (code "20") (name "INB_M2") (class "Default")
      (node (ref "J3") (pin "20") (pinfunction "20_20") (pintype "bidirectional"))
      (node (ref "J5") (pin "20") (pinfunction "20_20") (pintype "bidirectional"))
    )
    (net (code "21") (name "JACK") (class "Default")
      (node (ref "J3") (pin "28") (pinfunction "28_28") (pintype "bidirectional"))
      (node (ref "J5") (pin "28") (pinfunction "28_28") (pintype "bidirectional"))
    )
    (net (code "22") (name "MISO") (class "Default")
      (node (ref "R11") (pin "2") (pinfunction "2_2") (pintype "passive"))
      (node (ref "STM32") (pin "12") (pinfunction "PA6_12") (pintype "bidirectional"))
    )
    (net (code "23") (name "MONITORING_ALIM_APU") (class "Default")
      (node (ref "J4") (pin "13") (pinfunction "13_13") (pintype "bidirectional"))
      (node (ref "J6") (pin "13") (pinfunction "13_13") (pintype "bidirectional"))
      (node (ref "STM32") (pin "28") (pinfunction "PB5_28") (pintype "bidirectional"))
    )
    (net (code "24") (name "MONITORING_ALIM_MOTOR") (class "Default")
      (node (ref "J3") (pin "34") (pinfunction "34_34") (pintype "bidirectional"))
      (node (ref "J5") (pin "34") (pinfunction "34_34") (pintype "bidirectional"))
    )
    (net (code "25") (name "MONITORING_ALIM_SEQ") (class "Default")
      (node (ref "J3") (pin "36") (pinfunction "36_36") (pintype "bidirectional"))
      (node (ref "J5") (pin "36") (pinfunction "36_36") (pintype "bidirectional"))
    )
    (net (code "26") (name "MOSI") (class "Default")
      (node (ref "R12") (pin "2") (pinfunction "2_2") (pintype "passive"))
      (node (ref "STM32") (pin "13") (pinfunction "PA7_13") (pintype "bidirectional"))
    )
    (net (code "27") (name "N301") (class "Default")
      (node (ref "BMP") (pin "3") (pinfunction "SDI_3") (pintype "bidirectional"))
      (node (ref "R3") (pin "2") (pinfunction "2_2") (pintype "passive"))
    )
    (net (code "28") (name "N303") (class "Default")
      (node (ref "BMP") (pin "4") (pinfunction "SCK_4") (pintype "input"))
      (node (ref "R4") (pin "2") (pinfunction "2_2") (pintype "passive"))
    )
    (net (code "29") (name "NRST") (class "Default")
      (node (ref "C14") (pin "1") (pinfunction "1_1") (pintype "passive"))
      (node (ref "J2") (pin "3") (pinfunction "3_3") (pintype "bidirectional"))
      (node (ref "R16") (pin "2") (pinfunction "2_2") (pintype "passive"))
      (node (ref "STM32") (pin "4") (pinfunction "NRST_4") (pintype "bidirectional"))
    )
    (net (code "30") (name "Net-(D1-ANODE)") (class "Default")
      (node (ref "D1") (pin "2") (pinfunction "ANODE_2") (pintype "passive"))
      (node (ref "R15") (pin "2") (pinfunction "2_2") (pintype "passive"))
    )
    (net (code "31") (name "Net-(D2-ANODE)") (class "Default")
      (node (ref "D2") (pin "2") (pinfunction "ANODE_2") (pintype "passive"))
      (node (ref "R14") (pin "2") (pinfunction "2_2") (pintype "passive"))
    )
    (net (code "32") (name "Net-(D3-ANODE)") (class "Default")
      (node (ref "D3") (pin "2") (pinfunction "ANODE_2") (pintype "passive"))
      (node (ref "R19") (pin "2") (pinfunction "2_2") (pintype "passive"))
    )
    (net (code "33") (name "Net-(D4-ANODE)") (class "Default")
      (node (ref "D4") (pin "2") (pinfunction "ANODE_2") (pintype "passive"))
      (node (ref "R20") (pin "2") (pinfunction "2_2") (pintype "passive"))
    )
    (net (code "34") (name "Net-(DS-SCL)") (class "Default")
      (node (ref "DS") (pin "16") (pinfunction "SCL_16") (pintype "input"))
      (node (ref "R8") (pin "1") (pinfunction "1_1") (pintype "passive"))
    )
    (net (code "35") (name "Net-(DS-SDA)") (class "Default")
      (node (ref "DS") (pin "15") (pinfunction "SDA_15") (pintype "bidirectional"))
      (node (ref "R7") (pin "1") (pinfunction "1_1") (pintype "passive"))
    )
    (net (code "36") (name "Net-(DS-~{RST})") (class "Default")
      (node (ref "DS") (pin "4") (pinfunction "~{RST}_4") (pintype "bidirectional"))
      (node (ref "R9") (pin "1") (pinfunction "1_1") (pintype "passive"))
    )
    (net (code "37") (name "Net-(J1-CLK)") (class "Default")
      (node (ref "J1") (pin "5") (pinfunction "CLK_5") (pintype "bidirectional"))
      (node (ref "R13") (pin "1") (pinfunction "1_1") (pintype "passive"))
    )
    (net (code "38") (name "Net-(J1-CMD)") (class "Default")
      (node (ref "J1") (pin "3") (pinfunction "CMD_3") (pintype "bidirectional"))
      (node (ref "R12") (pin "1") (pinfunction "1_1") (pintype "passive"))
    )
    (net (code "39") (name "Net-(J1-DAT0)") (class "Default")
      (node (ref "J1") (pin "7") (pinfunction "DAT0_7") (pintype "bidirectional"))
      (node (ref "R11") (pin "1") (pinfunction "1_1") (pintype "passive"))
    )
    (net (code "40") (name "Net-(MPU-CPOUT)") (class "Default")
      (node (ref "C12") (pin "2") (pinfunction "2_2") (pintype "passive"))
      (node (ref "MPU") (pin "20") (pinfunction "CPOUT_20") (pintype "passive"))
    )
    (net (code "41") (name "Net-(MPU-REGOUT)") (class "Default")
      (node (ref "C13") (pin "2") (pinfunction "2_2") (pintype "passive"))
      (node (ref "MPU") (pin "10") (pinfunction "REGOUT_10") (pintype "passive"))
    )
    (net (code "42") (name "Net-(MPU-SCL)") (class "Default")
      (node (ref "MPU") (pin "23") (pinfunction "SCL_23") (pintype "input"))
      (node (ref "R1") (pin "2") (pinfunction "2_2") (pintype "passive"))
    )
    (net (code "43") (name "Net-(MPU-SDA)") (class "Default")
      (node (ref "MPU") (pin "24") (pinfunction "SDA_24") (pintype "bidirectional"))
      (node (ref "R2") (pin "2") (pinfunction "2_2") (pintype "passive"))
    )
    (net (code "44") (name "Net-(R16-Pad1)") (class "Default")
      (node (ref "R16") (pin "1") (pinfunction "1_1") (pintype "passive"))
      (node (ref "SW1") (pin "2") (pinfunction "2_2") (pintype "passive"))
    )
    (net (code "45") (name "Net-(STM32-BOOT0)") (class "Default")
      (node (ref "R10") (pin "2") (pinfunction "2_2") (pintype "passive"))
      (node (ref "STM32") (pin "31") (pinfunction "BOOT0_31") (pintype "input"))
    )
    (net (code "46") (name "Net-(STM32-PA9)") (class "Default")
      (node (ref "R22") (pin "2") (pinfunction "2_2") (pintype "passive"))
      (node (ref "STM32") (pin "19") (pinfunction "PA9_19") (pintype "bidirectional"))
    )
    (net (code "47") (name "Net-(STM32-PA10)") (class "Default")
      (node (ref "R23") (pin "2") (pinfunction "2_2") (pintype "passive"))
      (node (ref "STM32") (pin "20") (pinfunction "PA10_20") (pintype "bidirectional"))
    )
    (net (code "48") (name "Net-(STM32-VDDA{slash}VREF+)") (class "Default")
      (node (ref "C8") (pin "1") (pinfunction "1_1") (pintype "passive"))
      (node (ref "FB1") (pin "1") (pinfunction "1_1") (pintype "passive"))
      (node (ref "STM32") (pin "5") (pinfunction "VDDA/VREF+_5") (pintype "power_in"))
    )
    (net (code "49") (name "PWM_M1") (class "Default")
      (node (ref "J3") (pin "30") (pinfunction "30_30") (pintype "bidirectional"))
      (node (ref "J5") (pin "30") (pinfunction "30_30") (pintype "bidirectional"))
    )
    (net (code "50") (name "PWM_M2") (class "Default")
      (node (ref "J3") (pin "32") (pinfunction "32_32") (pintype "bidirectional"))
      (node (ref "J5") (pin "32") (pinfunction "32_32") (pintype "bidirectional"))
    )
    (net (code "51") (name "RST_DS") (class "Default")
      (node (ref "R9") (pin "2") (pinfunction "2_2") (pintype "passive"))
      (node (ref "STM32") (pin "3") (pinfunction "PF1/OSC_OUT_3") (pintype "bidirectional"))
    )
    (net (code "52") (name "RX_APU") (class "Default")
      (node (ref "J4") (pin "11") (pinfunction "11_11") (pintype "bidirectional"))
      (node (ref "J6") (pin "11") (pinfunction "11_11") (pintype "bidirectional"))
      (node (ref "STM32") (pin "27") (pinfunction "PB4_27") (pintype "bidirectional"))
    )
    (net (code "53") (name "RX_LTS") (class "Default")
      (node (ref "J7") (pin "1") (pinfunction "1_1") (pintype "bidirectional"))
      (node (ref "R20") (pin "1") (pinfunction "1_1") (pintype "passive"))
      (node (ref "R23") (pin "1") (pinfunction "1_1") (pintype "passive"))
    )
    (net (code "54") (name "SCL") (class "Default")
      (node (ref "J8") (pin "5") (pinfunction "5_5") (pintype "bidirectional"))
      (node (ref "R1") (pin "1") (pinfunction "1_1") (pintype "passive"))
      (node (ref "R4") (pin "1") (pinfunction "1_1") (pintype "passive"))
      (node (ref "R6") (pin "1") (pinfunction "1_1") (pintype "passive"))
      (node (ref "R8") (pin "2") (pinfunction "2_2") (pintype "passive"))
      (node (ref "STM32") (pin "29") (pinfunction "PB6_29") (pintype "bidirectional"))
    )
    (net (code "55") (name "SCLK") (class "Default")
      (node (ref "R13") (pin "2") (pinfunction "2_2") (pintype "passive"))
      (node (ref "STM32") (pin "11") (pinfunction "PA5_11") (pintype "bidirectional"))
    )
    (net (code "56") (name "SCL_SEQ") (class "Default")
      (node (ref "J3") (pin "38") (pinfunction "38_38") (pintype "bidirectional"))
      (node (ref "J5") (pin "38") (pinfunction "38_38") (pintype "bidirectional"))
    )
    (net (code "57") (name "SDA") (class "Default")
      (node (ref "J8") (pin "3") (pinfunction "3_3") (pintype "bidirectional"))
      (node (ref "R2") (pin "1") (pinfunction "1_1") (pintype "passive"))
      (node (ref "R3") (pin "1") (pinfunction "1_1") (pintype "passive"))
      (node (ref "R5") (pin "1") (pinfunction "1_1") (pintype "passive"))
      (node (ref "R7") (pin "2") (pinfunction "2_2") (pintype "passive"))
      (node (ref "STM32") (pin "30") (pinfunction "PB7_30") (pintype "bidirectional"))
    )
    (net (code "58") (name "SDA_SEQ") (class "Default")
      (node (ref "J3") (pin "40") (pinfunction "40_40") (pintype "bidirectional"))
      (node (ref "J5") (pin "40") (pinfunction "40_40") (pintype "bidirectional"))
    )
    (net (code "59") (name "SWCLK") (class "Default")
      (node (ref "J2") (pin "4") (pinfunction "4_4") (pintype "bidirectional"))
      (node (ref "STM32") (pin "24") (pinfunction "PA14_24") (pintype "bidirectional"))
    )
    (net (code "60") (name "SWDIO") (class "Default")
      (node (ref "J2") (pin "2") (pinfunction "2_2") (pintype "bidirectional"))
      (node (ref "R14") (pin "1") (pinfunction "1_1") (pintype "passive"))
      (node (ref "STM32") (pin "23") (pinfunction "PA13_23") (pintype "bidirectional"))
    )
    (net (code "61") (name "TX_APU") (class "Default")
      (node (ref "J4") (pin "9") (pinfunction "9_9") (pintype "bidirectional"))
      (node (ref "J6") (pin "9") (pinfunction "9_9") (pintype "bidirectional"))
      (node (ref "STM32") (pin "26") (pinfunction "PB3_26") (pintype "bidirectional"))
    )
    (net (code "62") (name "TX_LTS") (class "Default")
      (node (ref "J7") (pin "3") (pinfunction "3_3") (pintype "bidirectional"))
      (node (ref "R19") (pin "1") (pinfunction "1_1") (pintype "passive"))
      (node (ref "R22") (pin "1") (pinfunction "1_1") (pintype "passive"))
    )
    (net (code "63") (name "unconnected-(DS-32KHZ-Pad1)") (class "Default")
      (node (ref "DS") (pin "1") (pinfunction "32KHZ_1") (pintype "output"))
    )
    (net (code "64") (name "unconnected-(DS-~{INT{slash}SQW}-Pad3)") (class "Default")
      (node (ref "DS") (pin "3") (pinfunction "~{INT/SQW}_3") (pintype "output"))
    )
    (net (code "65") (name "unconnected-(J1-DAT1-Pad8)") (class "Default")
      (node (ref "J1") (pin "8") (pinfunction "DAT1_8") (pintype "bidirectional"))
    )
    (net (code "66") (name "unconnected-(J1-DAT2-Pad1)") (class "Default")
      (node (ref "J1") (pin "1") (pinfunction "DAT2_1") (pintype "bidirectional"))
    )
    (net (code "67") (name "unconnected-(J2-Pad6)") (class "Default")
      (node (ref "J2") (pin "6") (pinfunction "6_6") (pintype "bidirectional"))
    )
    (net (code "68") (name "unconnected-(J7-PadMP1)") (class "Default")
      (node (ref "J7") (pin "MP1") (pinfunction "MP1_MP1") (pintype "bidirectional"))
    )
    (net (code "69") (name "unconnected-(J7-PadMP2)") (class "Default")
      (node (ref "J7") (pin "MP2") (pinfunction "MP2_MP2") (pintype "bidirectional"))
    )
    (net (code "70") (name "unconnected-(J8-PadMP1)") (class "Default")
      (node (ref "J8") (pin "MP1") (pinfunction "MP1_MP1") (pintype "bidirectional"))
    )
    (net (code "71") (name "unconnected-(J8-PadMP2)") (class "Default")
      (node (ref "J8") (pin "MP2") (pinfunction "MP2_MP2") (pintype "bidirectional"))
    )
    (net (code "72") (name "unconnected-(MPU-AUX_CL-Pad7)") (class "Default")
      (node (ref "MPU") (pin "7") (pinfunction "AUX_CL_7") (pintype "input"))
    )
    (net (code "73") (name "unconnected-(MPU-AUX_DA-Pad6)") (class "Default")
      (node (ref "MPU") (pin "6") (pinfunction "AUX_DA_6") (pintype "bidirectional"))
    )
    (net (code "74") (name "unconnected-(MPU-INT-Pad12)") (class "Default")
      (node (ref "MPU") (pin "12") (pinfunction "INT_12") (pintype "output"))
    )
    (net (code "75") (name "unconnected-(MPU-RESV-Pad19)") (class "Default")
      (node (ref "MPU") (pin "19") (pinfunction "RESV_19") (pintype "passive"))
    )
    (net (code "76") (name "unconnected-(MPU-RESV-Pad21)") (class "Default")
      (node (ref "MPU") (pin "21") (pinfunction "RESV_21") (pintype "passive"))
    )
    (net (code "77") (name "unconnected-(MPU-RESV-Pad22)") (class "Default")
      (node (ref "MPU") (pin "22") (pinfunction "RESV_22") (pintype "passive"))
    )
    (net (code "78") (name "unconnected-(STM32-PA0-Pad6)") (class "Default")
      (node (ref "STM32") (pin "6") (pinfunction "PA0_6") (pintype "bidirectional"))
    )
    (net (code "79") (name "unconnected-(STM32-PA1-Pad7)") (class "Default")
      (node (ref "STM32") (pin "7") (pinfunction "PA1_7") (pintype "bidirectional"))
    )
    (net (code "80") (name "unconnected-(STM32-PA8-Pad18)") (class "Default")
      (node (ref "STM32") (pin "18") (pinfunction "PA8_18") (pintype "bidirectional"))
    )
    (net (code "81") (name "unconnected-(STM32-PA11-Pad21)") (class "Default")
      (node (ref "STM32") (pin "21") (pinfunction "PA11_21") (pintype "bidirectional"))
    )
    (net (code "82") (name "unconnected-(STM32-PA12-Pad22)") (class "Default")
      (node (ref "STM32") (pin "22") (pinfunction "PA12_22") (pintype "bidirectional"))
    )
    (net (code "83") (name "unconnected-(STM32-PA15-Pad25)") (class "Default")
      (node (ref "STM32") (pin "25") (pinfunction "PA15_25") (pintype "bidirectional"))
    )
    (net (code "84") (name "unconnected-(STM32-PB0-Pad14)") (class "Default")
      (node (ref "STM32") (pin "14") (pinfunction "PB0_14") (pintype "bidirectional"))
    )
    (net (code "85") (name "unconnected-(STM32-PB1-Pad15)") (class "Default")
      (node (ref "STM32") (pin "15") (pinfunction "PB1_15") (pintype "bidirectional"))
    )
  )
)
